# TI74_RAM_v2.net
KiCad netlist of a schematic drawn in EAGLE
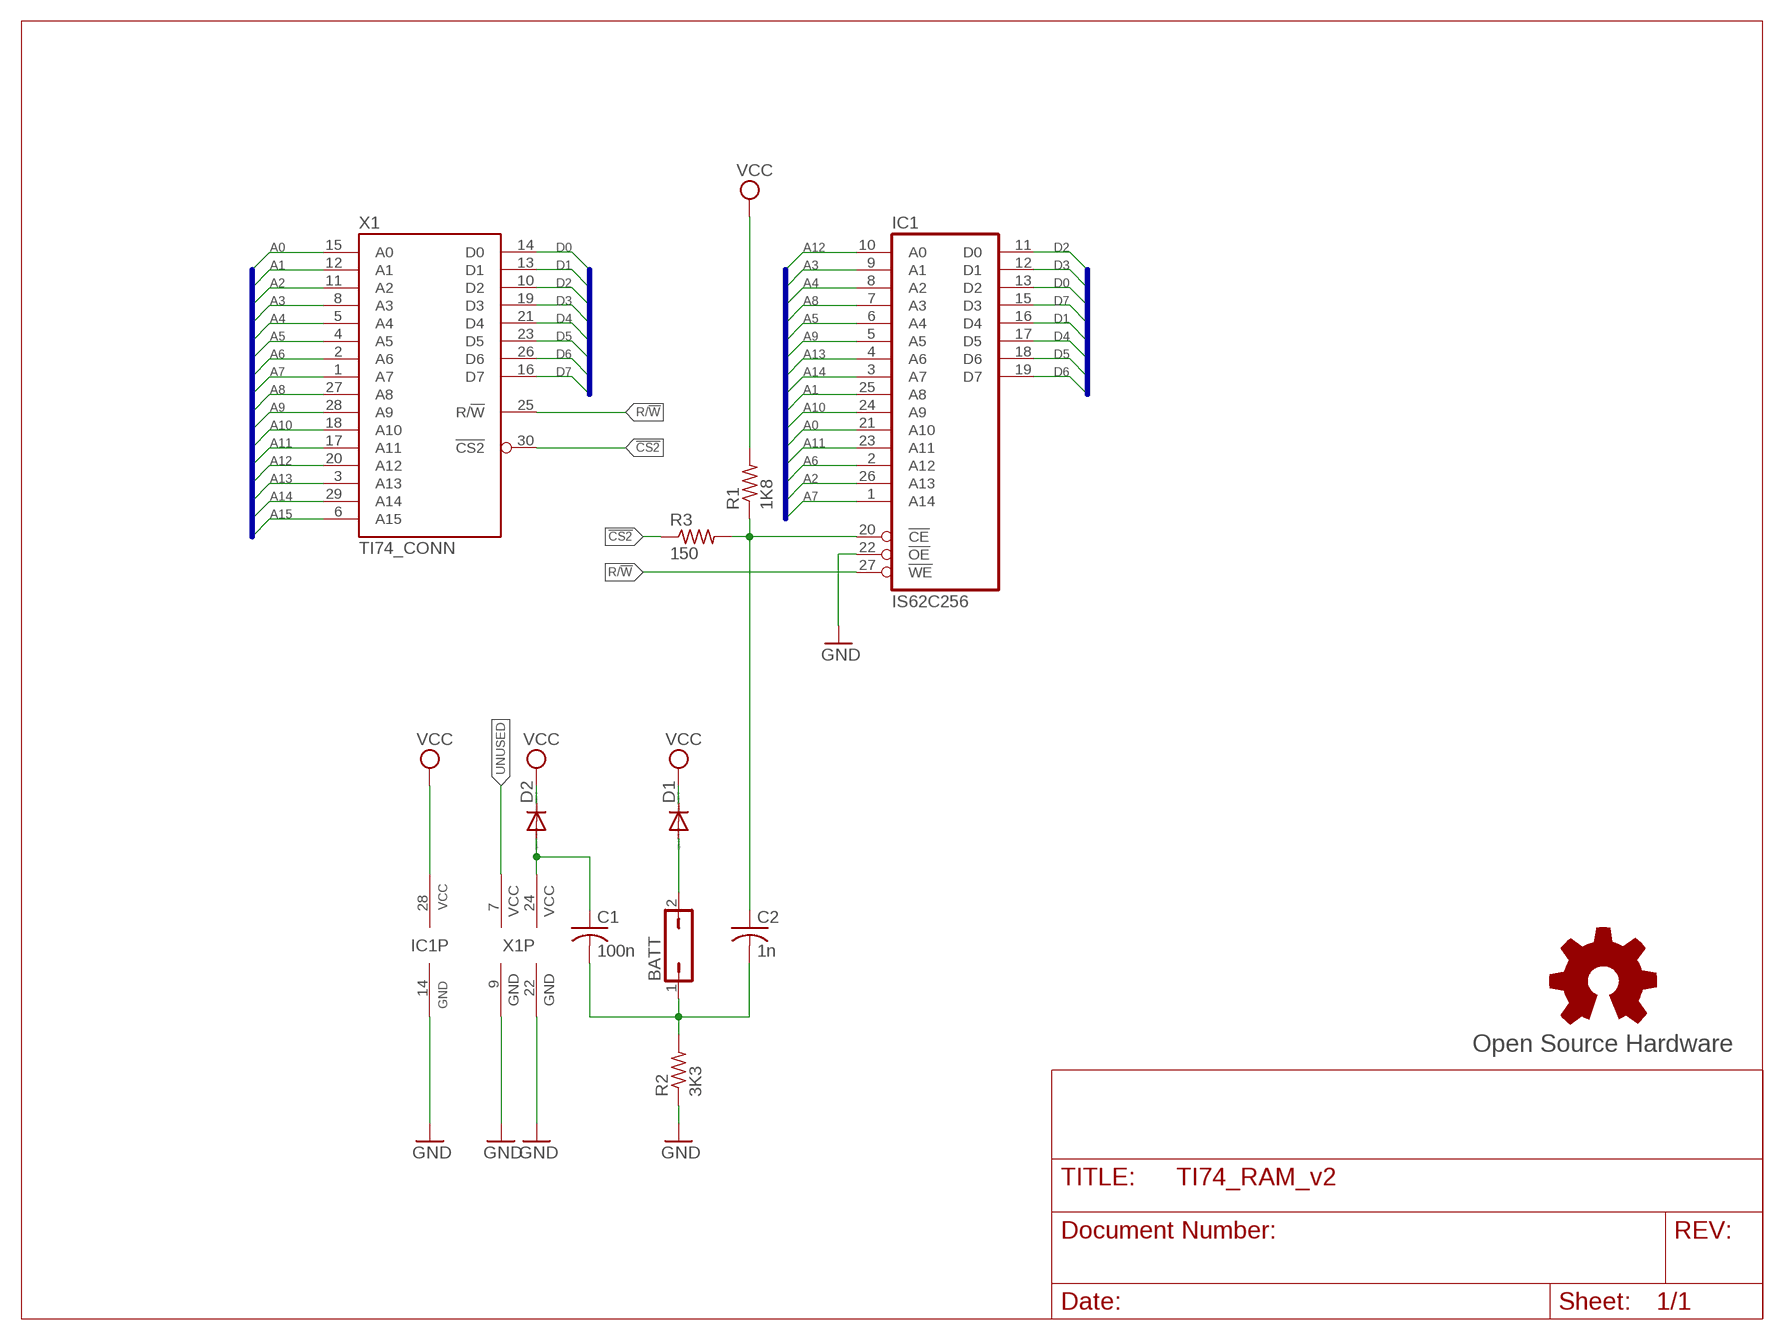
[diagram p0: schematic, sheet 1]

(export (version "E")
  (design (tool "Eeschema 10.0.6"))
  (components
    (comp (ref "BATT")
      (value "JP1Q")
      (footprint "eagle-import:JP1")
      (libsource (lib "eagle-import") (part "JP1Q"))
    )
    (comp (ref "C1")
      (value "100n")
      (footprint "eagle-import:C0603")
      (libsource (lib "eagle-import") (part "C-USC0603"))
    )
    (comp (ref "C2")
      (value "1n")
      (footprint "eagle-import:C0603")
      (libsource (lib "eagle-import") (part "C-USC0603"))
    )
    (comp (ref "D1")
      (value "DIODE-SOD323-W")
      (footprint "eagle-import:SOD323-W")
      (libsource (lib "eagle-import") (part "DIODE-SOD323-W"))
    )
    (comp (ref "D2")
      (value "DIODE-SOD323-W")
      (footprint "eagle-import:SOD323-W")
      (libsource (lib "eagle-import") (part "DIODE-SOD323-W"))
    )
    (comp (ref "GOLD_ORB_SM1")
      (value "Open Source Hardware")
      (footprint "eagle-import:OSHW_5MM")
      (libsource (lib "eagle-import") (part "OSHWLOGOLOGO5MM"))
    )
    (comp (ref "IC1")
      (value "IS62C256")
      (footprint "eagle-import:SO28L")
      (fields (field (name "MPN") "CY62256VNLL-70SNXI"))
      (libsource (lib "eagle-import") (part "JEDEC_32KB_SRAM"))
    )
    (comp (ref "R1")
      (value "1K8")
      (footprint "eagle-import:R0603")
      (libsource (lib "eagle-import") (part "R-US_R0603"))
    )
    (comp (ref "R2")
      (value "3K3")
      (footprint "eagle-import:R0603")
      (libsource (lib "eagle-import") (part "R-US_R0603"))
    )
    (comp (ref "R3")
      (value "150")
      (footprint "eagle-import:R0603")
      (libsource (lib "eagle-import") (part "R-US_R0603"))
    )
    (comp (ref "X1")
      (value "TI74_CONN")
      (footprint "eagle-import:MA050-15-2SHORT")
      (libsource (lib "eagle-import") (part "TI74_CONN"))
    )
  )
  (nets
    (net (code "1") (name "/A0") (class "Default")
      (node (ref "IC1") (pin "21") (pinfunction "A10_21") (pintype "input"))
      (node (ref "X1") (pin "15") (pinfunction "A0_15") (pintype "bidirectional"))
    )
    (net (code "2") (name "/A1") (class "Default")
      (node (ref "IC1") (pin "25") (pinfunction "A8_25") (pintype "input"))
      (node (ref "X1") (pin "12") (pinfunction "A1_12") (pintype "bidirectional"))
    )
    (net (code "3") (name "/A2") (class "Default")
      (node (ref "IC1") (pin "26") (pinfunction "A13_26") (pintype "input"))
      (node (ref "X1") (pin "11") (pinfunction "A2_11") (pintype "bidirectional"))
    )
    (net (code "4") (name "/A3") (class "Default")
      (node (ref "IC1") (pin "9") (pinfunction "A1_9") (pintype "input"))
      (node (ref "X1") (pin "8") (pinfunction "A3_8") (pintype "bidirectional"))
    )
    (net (code "5") (name "/A4") (class "Default")
      (node (ref "IC1") (pin "8") (pinfunction "A2_8") (pintype "input"))
      (node (ref "X1") (pin "5") (pinfunction "A4_5") (pintype "bidirectional"))
    )
    (net (code "6") (name "/A5") (class "Default")
      (node (ref "IC1") (pin "6") (pinfunction "A4_6") (pintype "input"))
      (node (ref "X1") (pin "4") (pinfunction "A5_4") (pintype "bidirectional"))
    )
    (net (code "7") (name "/A6") (class "Default")
      (node (ref "IC1") (pin "2") (pinfunction "A12_2") (pintype "input"))
      (node (ref "X1") (pin "2") (pinfunction "A6_2") (pintype "bidirectional"))
    )
    (net (code "8") (name "/A7") (class "Default")
      (node (ref "IC1") (pin "1") (pinfunction "A14_1") (pintype "input"))
      (node (ref "X1") (pin "1") (pinfunction "A7_1") (pintype "bidirectional"))
    )
    (net (code "9") (name "/A8") (class "Default")
      (node (ref "IC1") (pin "7") (pinfunction "A3_7") (pintype "input"))
      (node (ref "X1") (pin "27") (pinfunction "A8_27") (pintype "bidirectional"))
    )
    (net (code "10") (name "/A9") (class "Default")
      (node (ref "IC1") (pin "5") (pinfunction "A5_5") (pintype "input"))
      (node (ref "X1") (pin "28") (pinfunction "A9_28") (pintype "bidirectional"))
    )
    (net (code "11") (name "/A10") (class "Default")
      (node (ref "IC1") (pin "24") (pinfunction "A9_24") (pintype "input"))
      (node (ref "X1") (pin "18") (pinfunction "A10_18") (pintype "bidirectional"))
    )
    (net (code "12") (name "/A11") (class "Default")
      (node (ref "IC1") (pin "23") (pinfunction "A11_23") (pintype "input"))
      (node (ref "X1") (pin "17") (pinfunction "A11_17") (pintype "bidirectional"))
    )
    (net (code "13") (name "/A12") (class "Default")
      (node (ref "IC1") (pin "10") (pinfunction "A0_10") (pintype "input"))
      (node (ref "X1") (pin "20") (pinfunction "A12_20") (pintype "bidirectional"))
    )
    (net (code "14") (name "/A13") (class "Default")
      (node (ref "IC1") (pin "4") (pinfunction "A6_4") (pintype "input"))
      (node (ref "X1") (pin "3") (pinfunction "A13_3") (pintype "bidirectional"))
    )
    (net (code "15") (name "/A14") (class "Default")
      (node (ref "IC1") (pin "3") (pinfunction "A7_3") (pintype "input"))
      (node (ref "X1") (pin "29") (pinfunction "A14_29") (pintype "bidirectional"))
    )
    (net (code "16") (name "/A15") (class "Default")
      (node (ref "X1") (pin "6") (pinfunction "A15_6") (pintype "bidirectional"))
    )
    (net (code "17") (name "/D0") (class "Default")
      (node (ref "IC1") (pin "13") (pinfunction "D2_13") (pintype "bidirectional"))
      (node (ref "X1") (pin "14") (pinfunction "D0_14") (pintype "bidirectional"))
    )
    (net (code "18") (name "/D1") (class "Default")
      (node (ref "IC1") (pin "16") (pinfunction "D4_16") (pintype "bidirectional"))
      (node (ref "X1") (pin "13") (pinfunction "D1_13") (pintype "bidirectional"))
    )
    (net (code "19") (name "/D2") (class "Default")
      (node (ref "IC1") (pin "11") (pinfunction "D0_11") (pintype "bidirectional"))
      (node (ref "X1") (pin "10") (pinfunction "D2_10") (pintype "bidirectional"))
    )
    (net (code "20") (name "/D3") (class "Default")
      (node (ref "IC1") (pin "12") (pinfunction "D1_12") (pintype "bidirectional"))
      (node (ref "X1") (pin "19") (pinfunction "D3_19") (pintype "bidirectional"))
    )
    (net (code "21") (name "/D4") (class "Default")
      (node (ref "IC1") (pin "17") (pinfunction "D5_17") (pintype "bidirectional"))
      (node (ref "X1") (pin "21") (pinfunction "D4_21") (pintype "bidirectional"))
    )
    (net (code "22") (name "/D5") (class "Default")
      (node (ref "IC1") (pin "18") (pinfunction "D6_18") (pintype "bidirectional"))
      (node (ref "X1") (pin "23") (pinfunction "D5_23") (pintype "bidirectional"))
    )
    (net (code "23") (name "/D6") (class "Default")
      (node (ref "IC1") (pin "19") (pinfunction "D7_19") (pintype "bidirectional"))
      (node (ref "X1") (pin "26") (pinfunction "D6_26") (pintype "bidirectional"))
    )
    (net (code "24") (name "/D7") (class "Default")
      (node (ref "IC1") (pin "15") (pinfunction "D3_15") (pintype "bidirectional"))
      (node (ref "X1") (pin "16") (pinfunction "D7_16") (pintype "bidirectional"))
    )
    (net (code "25") (name "/R{slash}~{W}") (class "Default")
      (node (ref "IC1") (pin "27") (pinfunction "~{WE}_27") (pintype "input"))
      (node (ref "X1") (pin "25") (pinfunction "R/~{W}_25") (pintype "bidirectional"))
    )
    (net (code "26") (name "/~{CS2}") (class "Default")
      (node (ref "R3") (pin "1") (pinfunction "1_1") (pintype "passive"))
      (node (ref "X1") (pin "30") (pinfunction "~{CS2}_30") (pintype "bidirectional"))
    )
    (net (code "27") (name "GND") (class "Default")
      (node (ref "IC1") (pin "14") (pinfunction "GND_14") (pintype "power_in"))
      (node (ref "IC1") (pin "22") (pinfunction "~{OE}_22") (pintype "input"))
      (node (ref "R2") (pin "1") (pinfunction "1_1") (pintype "passive"))
      (node (ref "X1") (pin "22") (pinfunction "GND_22") (pintype "power_in"))
      (node (ref "X1") (pin "9") (pinfunction "GND_9") (pintype "power_in"))
    )
    (net (code "28") (name "Net-(BATT-Pad1)") (class "Default")
      (node (ref "BATT") (pin "1") (pinfunction "1_1") (pintype "passive"))
      (node (ref "C1") (pin "2") (pinfunction "2_2") (pintype "passive"))
      (node (ref "C2") (pin "2") (pinfunction "2_2") (pintype "passive"))
      (node (ref "R2") (pin "2") (pinfunction "2_2") (pintype "passive"))
    )
    (net (code "29") (name "Net-(BATT-Pad2)") (class "Default")
      (node (ref "BATT") (pin "2") (pinfunction "2_2") (pintype "passive"))
      (node (ref "D1") (pin "A") (pinfunction "A_A") (pintype "passive"))
    )
    (net (code "30") (name "Net-(IC1A-~{CE})") (class "Default")
      (node (ref "C2") (pin "1") (pinfunction "1_1") (pintype "passive"))
      (node (ref "IC1") (pin "20") (pinfunction "~{CE}_20") (pintype "input"))
      (node (ref "R1") (pin "1") (pinfunction "1_1") (pintype "passive"))
      (node (ref "R3") (pin "2") (pinfunction "2_2") (pintype "passive"))
    )
    (net (code "31") (name "Net-(X1B-VCC_RAM)") (class "Default")
      (node (ref "C1") (pin "1") (pinfunction "1_1") (pintype "passive"))
      (node (ref "D2") (pin "A") (pinfunction "A_A") (pintype "passive"))
      (node (ref "X1") (pin "24") (pinfunction "VCC_RAM_24") (pintype "power_in"))
    )
    (net (code "32") (name "UNUSED") (class "Default")
      (node (ref "X1") (pin "7") (pinfunction "VCC_7") (pintype "power_in"))
    )
    (net (code "33") (name "VCC") (class "Default")
      (node (ref "D1") (pin "C") (pinfunction "C_C") (pintype "passive"))
      (node (ref "D2") (pin "C") (pinfunction "C_C") (pintype "passive"))
      (node (ref "IC1") (pin "28") (pinfunction "VCC_28") (pintype "power_in"))
      (node (ref "R1") (pin "2") (pinfunction "2_2") (pintype "passive"))
    )
  )
)
